# CRUVI.net
KiCad netlist of a schematic drawn in Altium Designer
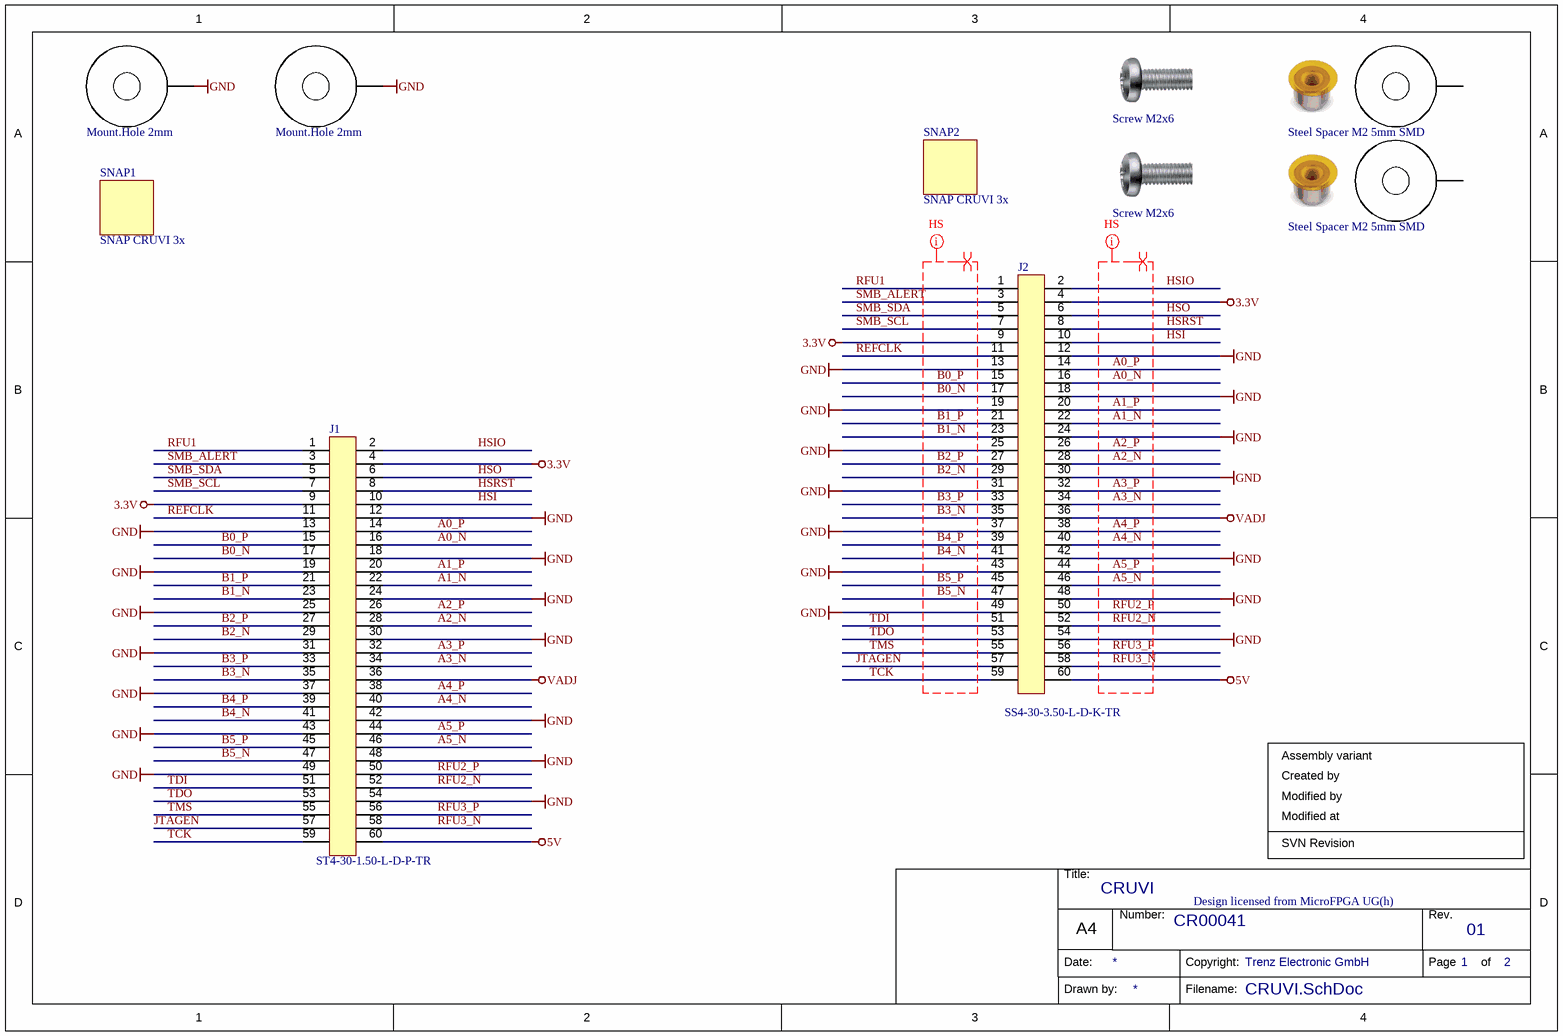
[diagram p0: CRUVI.SchDoc]

(export (version "E")
  (design (tool "Eeschema 10.0.6"))
  (components
    (comp (ref "H1") (value "Mount.Hole 2mm") (footprint "MHole2_2mm") (libsource (lib "TE") (part "MHole")))
    (comp (ref "H2") (value "Mount.Hole 2mm") (footprint "MHole2_2mm") (libsource (lib "TE") (part "MHole")))
    (comp (ref "H3")
      (value "Steel Spacer M2 5mm SMD")
      (footprint "9774050243")
      (description "9774050243R")
      (libsource (lib "TE") (part "MHole_wSpacer"))
    )
    (comp (ref "H4")
      (value "Steel Spacer M2 5mm SMD")
      (footprint "9774050243")
      (description "9774050243R")
      (libsource (lib "TE") (part "MHole_wSpacer"))
    )
    (comp (ref "J1")
      (value "ST4-30-1.50-L-D-P-TR")
      (footprint "ST4-30-1_50-L-D")
      (libsource (lib "TE") (part "CON-60"))
    )
    (comp (ref "J2")
      (value "SS4-30-3.50-L-D-K-TR")
      (footprint "SS4-30-3_50-L-D")
      (description "SS4-30-3.50-L-D-K")
      (libsource (lib "TE") (part "CON-60"))
    )
    (comp (ref "MECH1")
      (value "Screw M2x6")
      (description "Schraube M2x6mm")
      (libsource (lib "TE") (part "screw_m3x6"))
    )
    (comp (ref "MECH2")
      (value "Screw M2x6")
      (description "Schraube M2x6mm")
      (libsource (lib "TE") (part "screw_m3x6"))
    )
    (comp (ref "SNAP1")
      (value "SNAP CRUVI 3x")
      (footprint "CRUVI_3x_Snap")
      (description "SNAP for CRUVI 3x")
      (libsource (lib "TE") (part "DUMMY"))
    )
    (comp (ref "SNAP2")
      (value "SNAP CRUVI 3x")
      (footprint "CRUVI_3x_Snap")
      (description "SNAP for CRUVI 3x")
      (libsource (lib "TE") (part "DUMMY"))
    )
  )
  (nets
    (net (code "1") (name "/A0_N") (class "Default")
      (node (ref "J1") (pin "16") (pinfunction "16_16") (pintype "passive"))
      (node (ref "J2") (pin "16") (pinfunction "16_16") (pintype "passive"))
    )
    (net (code "2") (name "/A0_P") (class "Default")
      (node (ref "J1") (pin "14") (pinfunction "14_14") (pintype "passive"))
      (node (ref "J2") (pin "14") (pinfunction "14_14") (pintype "passive"))
    )
    (net (code "3") (name "/A1_N") (class "Default")
      (node (ref "J1") (pin "22") (pinfunction "22_22") (pintype "passive"))
      (node (ref "J2") (pin "22") (pinfunction "22_22") (pintype "passive"))
    )
    (net (code "4") (name "/A1_P") (class "Default")
      (node (ref "J1") (pin "20") (pinfunction "20_20") (pintype "passive"))
      (node (ref "J2") (pin "20") (pinfunction "20_20") (pintype "passive"))
    )
    (net (code "5") (name "/A2_N") (class "Default")
      (node (ref "J1") (pin "28") (pinfunction "28_28") (pintype "passive"))
      (node (ref "J2") (pin "28") (pinfunction "28_28") (pintype "passive"))
    )
    (net (code "6") (name "/A2_P") (class "Default")
      (node (ref "J1") (pin "26") (pinfunction "26_26") (pintype "passive"))
      (node (ref "J2") (pin "26") (pinfunction "26_26") (pintype "passive"))
    )
    (net (code "7") (name "/A3_N") (class "Default")
      (node (ref "J1") (pin "34") (pinfunction "34_34") (pintype "passive"))
      (node (ref "J2") (pin "34") (pinfunction "34_34") (pintype "passive"))
    )
    (net (code "8") (name "/A3_P") (class "Default")
      (node (ref "J1") (pin "32") (pinfunction "32_32") (pintype "passive"))
      (node (ref "J2") (pin "32") (pinfunction "32_32") (pintype "passive"))
    )
    (net (code "9") (name "/A4_N") (class "Default")
      (node (ref "J1") (pin "40") (pinfunction "40_40") (pintype "passive"))
      (node (ref "J2") (pin "40") (pinfunction "40_40") (pintype "passive"))
    )
    (net (code "10") (name "/A4_P") (class "Default")
      (node (ref "J1") (pin "38") (pinfunction "38_38") (pintype "passive"))
      (node (ref "J2") (pin "38") (pinfunction "38_38") (pintype "passive"))
    )
    (net (code "11") (name "/A5_N") (class "Default")
      (node (ref "J1") (pin "46") (pinfunction "46_46") (pintype "passive"))
      (node (ref "J2") (pin "46") (pinfunction "46_46") (pintype "passive"))
    )
    (net (code "12") (name "/A5_P") (class "Default")
      (node (ref "J1") (pin "44") (pinfunction "44_44") (pintype "passive"))
      (node (ref "J2") (pin "44") (pinfunction "44_44") (pintype "passive"))
    )
    (net (code "13") (name "/B0_N") (class "Default")
      (node (ref "J1") (pin "17") (pinfunction "17_17") (pintype "passive"))
      (node (ref "J2") (pin "17") (pinfunction "17_17") (pintype "passive"))
    )
    (net (code "14") (name "/B0_P") (class "Default")
      (node (ref "J1") (pin "15") (pinfunction "15_15") (pintype "passive"))
      (node (ref "J2") (pin "15") (pinfunction "15_15") (pintype "passive"))
    )
    (net (code "15") (name "/B1_N") (class "Default")
      (node (ref "J1") (pin "23") (pinfunction "23_23") (pintype "passive"))
      (node (ref "J2") (pin "23") (pinfunction "23_23") (pintype "passive"))
    )
    (net (code "16") (name "/B1_P") (class "Default")
      (node (ref "J1") (pin "21") (pinfunction "21_21") (pintype "passive"))
      (node (ref "J2") (pin "21") (pinfunction "21_21") (pintype "passive"))
    )
    (net (code "17") (name "/B2_N") (class "Default")
      (node (ref "J1") (pin "29") (pinfunction "29_29") (pintype "passive"))
      (node (ref "J2") (pin "29") (pinfunction "29_29") (pintype "passive"))
    )
    (net (code "18") (name "/B2_P") (class "Default")
      (node (ref "J1") (pin "27") (pinfunction "27_27") (pintype "passive"))
      (node (ref "J2") (pin "27") (pinfunction "27_27") (pintype "passive"))
    )
    (net (code "19") (name "/B3_N") (class "Default")
      (node (ref "J1") (pin "35") (pinfunction "35_35") (pintype "passive"))
      (node (ref "J2") (pin "35") (pinfunction "35_35") (pintype "passive"))
    )
    (net (code "20") (name "/B3_P") (class "Default")
      (node (ref "J1") (pin "33") (pinfunction "33_33") (pintype "passive"))
      (node (ref "J2") (pin "33") (pinfunction "33_33") (pintype "passive"))
    )
    (net (code "21") (name "/B4_N") (class "Default")
      (node (ref "J1") (pin "41") (pinfunction "41_41") (pintype "passive"))
      (node (ref "J2") (pin "41") (pinfunction "41_41") (pintype "passive"))
    )
    (net (code "22") (name "/B4_P") (class "Default")
      (node (ref "J1") (pin "39") (pinfunction "39_39") (pintype "passive"))
      (node (ref "J2") (pin "39") (pinfunction "39_39") (pintype "passive"))
    )
    (net (code "23") (name "/B5_N") (class "Default")
      (node (ref "J1") (pin "47") (pinfunction "47_47") (pintype "passive"))
      (node (ref "J2") (pin "47") (pinfunction "47_47") (pintype "passive"))
    )
    (net (code "24") (name "/B5_P") (class "Default")
      (node (ref "J1") (pin "45") (pinfunction "45_45") (pintype "passive"))
      (node (ref "J2") (pin "45") (pinfunction "45_45") (pintype "passive"))
    )
    (net (code "25") (name "/HSI") (class "Default")
      (node (ref "J1") (pin "10") (pinfunction "10_10") (pintype "passive"))
      (node (ref "J2") (pin "10") (pinfunction "10_10") (pintype "passive"))
    )
    (net (code "26") (name "/HSIO") (class "Default")
      (node (ref "J1") (pin "2") (pinfunction "2_2") (pintype "passive"))
      (node (ref "J2") (pin "2") (pinfunction "2_2") (pintype "passive"))
    )
    (net (code "27") (name "/HSO") (class "Default")
      (node (ref "J1") (pin "6") (pinfunction "6_6") (pintype "passive"))
      (node (ref "J2") (pin "6") (pinfunction "6_6") (pintype "passive"))
    )
    (net (code "28") (name "/HSRST") (class "Default")
      (node (ref "J1") (pin "8") (pinfunction "8_8") (pintype "passive"))
      (node (ref "J2") (pin "8") (pinfunction "8_8") (pintype "passive"))
    )
    (net (code "29") (name "/JTAGEN") (class "Default")
      (node (ref "J1") (pin "57") (pinfunction "57_57") (pintype "passive"))
      (node (ref "J2") (pin "57") (pinfunction "57_57") (pintype "passive"))
    )
    (net (code "30") (name "/REFCLK") (class "Default")
      (node (ref "J1") (pin "11") (pinfunction "11_11") (pintype "passive"))
      (node (ref "J2") (pin "11") (pinfunction "11_11") (pintype "passive"))
    )
    (net (code "31") (name "/RFU1") (class "Default")
      (node (ref "J1") (pin "1") (pinfunction "1_1") (pintype "passive"))
      (node (ref "J2") (pin "1") (pinfunction "1_1") (pintype "passive"))
    )
    (net (code "32") (name "/RFU2_N") (class "Default")
      (node (ref "J1") (pin "52") (pinfunction "52_52") (pintype "passive"))
      (node (ref "J2") (pin "52") (pinfunction "52_52") (pintype "passive"))
    )
    (net (code "33") (name "/RFU2_P") (class "Default")
      (node (ref "J1") (pin "50") (pinfunction "50_50") (pintype "passive"))
      (node (ref "J2") (pin "50") (pinfunction "50_50") (pintype "passive"))
    )
    (net (code "34") (name "/RFU3_N") (class "Default")
      (node (ref "J1") (pin "58") (pinfunction "58_58") (pintype "passive"))
      (node (ref "J2") (pin "58") (pinfunction "58_58") (pintype "passive"))
    )
    (net (code "35") (name "/RFU3_P") (class "Default")
      (node (ref "J1") (pin "56") (pinfunction "56_56") (pintype "passive"))
      (node (ref "J2") (pin "56") (pinfunction "56_56") (pintype "passive"))
    )
    (net (code "36") (name "/SMB_ALERT") (class "Default")
      (node (ref "J1") (pin "3") (pinfunction "3_3") (pintype "passive"))
      (node (ref "J2") (pin "3") (pinfunction "3_3") (pintype "passive"))
    )
    (net (code "37") (name "/SMB_SCL") (class "Default")
      (node (ref "J1") (pin "7") (pinfunction "7_7") (pintype "passive"))
      (node (ref "J2") (pin "7") (pinfunction "7_7") (pintype "passive"))
    )
    (net (code "38") (name "/SMB_SDA") (class "Default")
      (node (ref "J1") (pin "5") (pinfunction "5_5") (pintype "passive"))
      (node (ref "J2") (pin "5") (pinfunction "5_5") (pintype "passive"))
    )
    (net (code "39") (name "/TCK") (class "Default")
      (node (ref "J1") (pin "59") (pinfunction "59_59") (pintype "passive"))
      (node (ref "J2") (pin "59") (pinfunction "59_59") (pintype "passive"))
    )
    (net (code "40") (name "/TDI") (class "Default")
      (node (ref "J1") (pin "51") (pinfunction "51_51") (pintype "passive"))
      (node (ref "J2") (pin "51") (pinfunction "51_51") (pintype "passive"))
    )
    (net (code "41") (name "/TDO") (class "Default")
      (node (ref "J1") (pin "53") (pinfunction "53_53") (pintype "passive"))
      (node (ref "J2") (pin "53") (pinfunction "53_53") (pintype "passive"))
    )
    (net (code "42") (name "/TMS") (class "Default")
      (node (ref "J1") (pin "55") (pinfunction "55_55") (pintype "passive"))
      (node (ref "J2") (pin "55") (pinfunction "55_55") (pintype "passive"))
    )
    (net (code "43") (name "3.3V") (class "Default")
      (node (ref "J1") (pin "4") (pinfunction "4_4") (pintype "passive"))
      (node (ref "J1") (pin "9") (pinfunction "9_9") (pintype "passive"))
      (node (ref "J2") (pin "4") (pinfunction "4_4") (pintype "passive"))
      (node (ref "J2") (pin "9") (pinfunction "9_9") (pintype "passive"))
    )
    (net (code "44") (name "5V") (class "Default")
      (node (ref "J1") (pin "60") (pinfunction "60_60") (pintype "passive"))
      (node (ref "J2") (pin "60") (pinfunction "60_60") (pintype "passive"))
    )
    (net (code "45") (name "GND") (class "Default")
      (node (ref "H1") (pin "1") (pinfunction "1_1") (pintype "passive"))
      (node (ref "H2") (pin "1") (pinfunction "1_1") (pintype "passive"))
      (node (ref "J1") (pin "12") (pinfunction "12_12") (pintype "passive"))
      (node (ref "J1") (pin "13") (pinfunction "13_13") (pintype "passive"))
      (node (ref "J1") (pin "18") (pinfunction "18_18") (pintype "passive"))
      (node (ref "J1") (pin "19") (pinfunction "19_19") (pintype "passive"))
      (node (ref "J1") (pin "24") (pinfunction "24_24") (pintype "passive"))
      (node (ref "J1") (pin "25") (pinfunction "25_25") (pintype "passive"))
      (node (ref "J1") (pin "30") (pinfunction "30_30") (pintype "passive"))
      (node (ref "J1") (pin "31") (pinfunction "31_31") (pintype "passive"))
      (node (ref "J1") (pin "37") (pinfunction "37_37") (pintype "passive"))
      (node (ref "J1") (pin "42") (pinfunction "42_42") (pintype "passive"))
      (node (ref "J1") (pin "43") (pinfunction "43_43") (pintype "passive"))
      (node (ref "J1") (pin "48") (pinfunction "48_48") (pintype "passive"))
      (node (ref "J1") (pin "49") (pinfunction "49_49") (pintype "passive"))
      (node (ref "J1") (pin "54") (pinfunction "54_54") (pintype "passive"))
      (node (ref "J2") (pin "12") (pinfunction "12_12") (pintype "passive"))
      (node (ref "J2") (pin "13") (pinfunction "13_13") (pintype "passive"))
      (node (ref "J2") (pin "18") (pinfunction "18_18") (pintype "passive"))
      (node (ref "J2") (pin "19") (pinfunction "19_19") (pintype "passive"))
      (node (ref "J2") (pin "24") (pinfunction "24_24") (pintype "passive"))
      (node (ref "J2") (pin "25") (pinfunction "25_25") (pintype "passive"))
      (node (ref "J2") (pin "30") (pinfunction "30_30") (pintype "passive"))
      (node (ref "J2") (pin "31") (pinfunction "31_31") (pintype "passive"))
      (node (ref "J2") (pin "37") (pinfunction "37_37") (pintype "passive"))
      (node (ref "J2") (pin "42") (pinfunction "42_42") (pintype "passive"))
      (node (ref "J2") (pin "43") (pinfunction "43_43") (pintype "passive"))
      (node (ref "J2") (pin "48") (pinfunction "48_48") (pintype "passive"))
      (node (ref "J2") (pin "49") (pinfunction "49_49") (pintype "passive"))
      (node (ref "J2") (pin "54") (pinfunction "54_54") (pintype "passive"))
    )
    (net (code "46") (name "VADJ") (class "Default")
      (node (ref "J1") (pin "36") (pinfunction "36_36") (pintype "passive"))
      (node (ref "J2") (pin "36") (pinfunction "36_36") (pintype "passive"))
    )
    (net (code "47") (name "unconnected-(H3-Pad1)") (class "Default")
      (node (ref "H3") (pin "1") (pinfunction "1_1") (pintype "passive"))
    )
    (net (code "48") (name "unconnected-(H4-Pad1)") (class "Default")
      (node (ref "H4") (pin "1") (pinfunction "1_1") (pintype "passive"))
    )
  )
)
